# CactusCon7.net
KiCad netlist of a schematic drawn in EAGLE
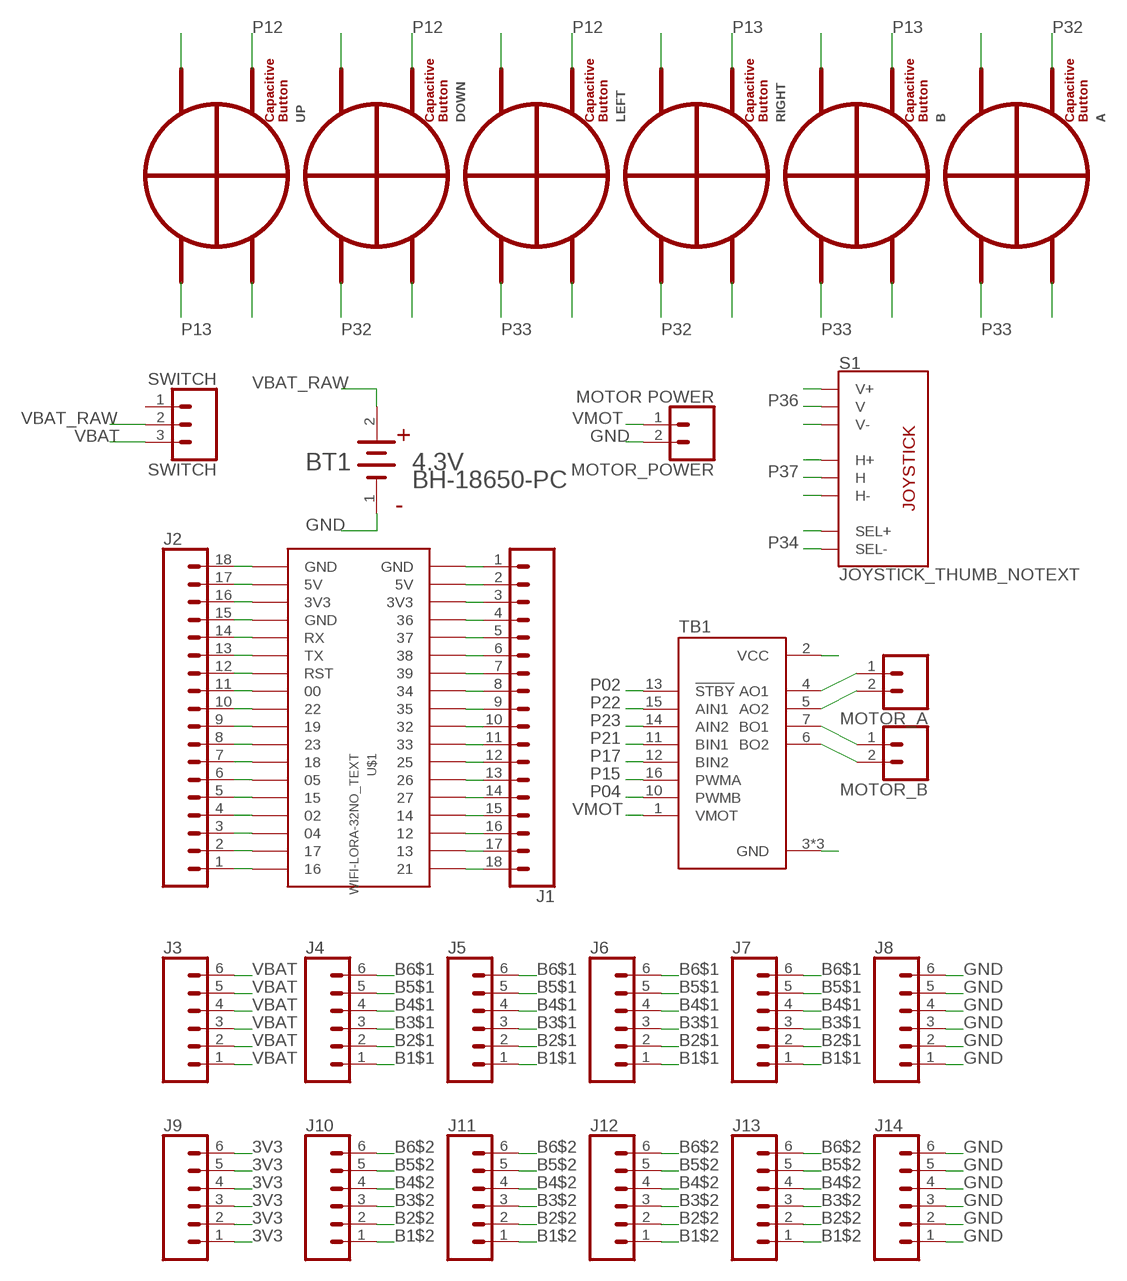
[diagram p0: schematic, sheet 1]

(export (version "E")
  (design (tool "Eeschema 10.0.6"))
  (components
    (comp (ref "A")
      (value "BUTTON_ACTIVE_QUADNO-LOGO")
      (footprint "eagle-import:BUTTON_ACTIVE_QUAD_10MM_NO_LOGO")
      (libsource (lib "eagle-import") (part "BUTTON_ACTIVE_QUADNO-LOGO"))
    )
    (comp (ref "B")
      (value "BUTTON_ACTIVE_QUADNO-LOGO")
      (footprint "eagle-import:BUTTON_ACTIVE_QUAD_10MM_NO_LOGO")
      (libsource (lib "eagle-import") (part "BUTTON_ACTIVE_QUADNO-LOGO"))
    )
    (comp (ref "BT1")
      (value "MPD_BH-18650-PCMPD_BH-18650-PC_0_0")
      (footprint "eagle-import:MPD_BH-18650-PC_0")
      (fields
        (field (name "DIGIKEY_PART_NUMBER") "BH-18650-PC-ND")
        (field (name "MF") "MPD")
        (field (name "MPN") "BH-18650-PC")
      )
      (libsource (lib "eagle-import") (part "MPD_BH-18650-PCMPD_BH-18650-PC_0_0"))
    )
    (comp (ref "DOWN")
      (value "BUTTON_ACTIVE_QUADNO-LOGO")
      (footprint "eagle-import:BUTTON_ACTIVE_QUAD_10MM_NO_LOGO")
      (libsource (lib "eagle-import") (part "BUTTON_ACTIVE_QUADNO-LOGO"))
    )
    (comp (ref "J1")
      (value "CONN_18")
      (footprint "eagle-import:1X18")
      (libsource (lib "eagle-import") (part "CONN_18"))
    )
    (comp (ref "J2")
      (value "CONN_18")
      (footprint "eagle-import:1X18")
      (libsource (lib "eagle-import") (part "CONN_18"))
    )
    (comp (ref "J3")
      (value "CONN_06NO_SILK_FEMALE_PTH")
      (footprint "eagle-import:1X06_NO_SILK")
      (libsource (lib "eagle-import") (part "CONN_06NO_SILK_FEMALE_PTH"))
    )
    (comp (ref "J4")
      (value "CONN_06NO_SILK_FEMALE_PTH")
      (footprint "eagle-import:1X06_NO_SILK")
      (libsource (lib "eagle-import") (part "CONN_06NO_SILK_FEMALE_PTH"))
    )
    (comp (ref "J5")
      (value "CONN_06NO_SILK_FEMALE_PTH")
      (footprint "eagle-import:1X06_NO_SILK")
      (libsource (lib "eagle-import") (part "CONN_06NO_SILK_FEMALE_PTH"))
    )
    (comp (ref "J6")
      (value "CONN_06NO_SILK_FEMALE_PTH")
      (footprint "eagle-import:1X06_NO_SILK")
      (libsource (lib "eagle-import") (part "CONN_06NO_SILK_FEMALE_PTH"))
    )
    (comp (ref "J7")
      (value "CONN_06NO_SILK_FEMALE_PTH")
      (footprint "eagle-import:1X06_NO_SILK")
      (libsource (lib "eagle-import") (part "CONN_06NO_SILK_FEMALE_PTH"))
    )
    (comp (ref "J8")
      (value "CONN_06NO_SILK_FEMALE_PTH")
      (footprint "eagle-import:1X06_NO_SILK")
      (libsource (lib "eagle-import") (part "CONN_06NO_SILK_FEMALE_PTH"))
    )
    (comp (ref "J9")
      (value "CONN_06NO_SILK_FEMALE_PTH")
      (footprint "eagle-import:1X06_NO_SILK")
      (libsource (lib "eagle-import") (part "CONN_06NO_SILK_FEMALE_PTH"))
    )
    (comp (ref "J10")
      (value "CONN_06NO_SILK_FEMALE_PTH")
      (footprint "eagle-import:1X06_NO_SILK")
      (libsource (lib "eagle-import") (part "CONN_06NO_SILK_FEMALE_PTH"))
    )
    (comp (ref "J11")
      (value "CONN_06NO_SILK_FEMALE_PTH")
      (footprint "eagle-import:1X06_NO_SILK")
      (libsource (lib "eagle-import") (part "CONN_06NO_SILK_FEMALE_PTH"))
    )
    (comp (ref "J12")
      (value "CONN_06NO_SILK_FEMALE_PTH")
      (footprint "eagle-import:1X06_NO_SILK")
      (libsource (lib "eagle-import") (part "CONN_06NO_SILK_FEMALE_PTH"))
    )
    (comp (ref "J13")
      (value "CONN_06NO_SILK_FEMALE_PTH")
      (footprint "eagle-import:1X06_NO_SILK")
      (libsource (lib "eagle-import") (part "CONN_06NO_SILK_FEMALE_PTH"))
    )
    (comp (ref "J14")
      (value "CONN_06NO_SILK_FEMALE_PTH")
      (footprint "eagle-import:1X06_NO_SILK")
      (libsource (lib "eagle-import") (part "CONN_06NO_SILK_FEMALE_PTH"))
    )
    (comp (ref "LEFT")
      (value "BUTTON_ACTIVE_QUADNO-LOGO")
      (footprint "eagle-import:BUTTON_ACTIVE_QUAD_10MM_NO_LOGO")
      (libsource (lib "eagle-import") (part "BUTTON_ACTIVE_QUADNO-LOGO"))
    )
    (comp (ref "MOTOR_A")
      (value "CONN_02")
      (footprint "eagle-import:1X02")
      (libsource (lib "eagle-import") (part "CONN_02"))
    )
    (comp (ref "MOTOR_B")
      (value "CONN_02")
      (footprint "eagle-import:1X02")
      (libsource (lib "eagle-import") (part "CONN_02"))
    )
    (comp (ref "MOTOR_POWER")
      (value "MOTOR POWER")
      (footprint "eagle-import:1X02")
      (libsource (lib "eagle-import") (part "CONN_02"))
    )
    (comp (ref "RIGHT")
      (value "BUTTON_ACTIVE_QUADNO-LOGO")
      (footprint "eagle-import:BUTTON_ACTIVE_QUAD_10MM_NO_LOGO")
      (libsource (lib "eagle-import") (part "BUTTON_ACTIVE_QUADNO-LOGO"))
    )
    (comp (ref "S1")
      (value "JOYSTICK_THUMB_NOTEXT")
      (footprint "eagle-import:JOYSTICK")
      (libsource (lib "eagle-import") (part "JOYSTICK_THUMB_NOTEXT"))
    )
    (comp (ref "SWITCH")
      (value "SWITCH")
      (footprint "eagle-import:1X03")
      (libsource (lib "eagle-import") (part "CONN_03"))
    )
    (comp (ref "TB1")
      (value "POLOLU-713ROB-14451")
      (footprint "eagle-import:SHIELD_POLOLU-713")
      (libsource (lib "eagle-import") (part "POLOLU-713ROB-14451"))
    )
    (comp (ref "U$1")
      (value "WIFI-LORA-32NO_TEXT")
      (footprint "eagle-import:2.54MM_2X18_NO_TEXT")
      (libsource (lib "eagle-import") (part "WIFI-LORA-32NO_TEXT"))
    )
    (comp (ref "UP")
      (value "BUTTON_ACTIVE_QUADNO-LOGO")
      (footprint "eagle-import:BUTTON_ACTIVE_QUAD_10MM_NO_LOGO")
      (libsource (lib "eagle-import") (part "BUTTON_ACTIVE_QUADNO-LOGO"))
    )
  )
  (nets
    (net (code "1") (name "/3V3") (class "Default")
      (node (ref "J1") (pin "3") (pinfunction "3_3") (pintype "passive"))
      (node (ref "J2") (pin "16") (pinfunction "16_16") (pintype "passive"))
      (node (ref "J9") (pin "1") (pinfunction "1_1") (pintype "passive"))
      (node (ref "J9") (pin "2") (pinfunction "2_2") (pintype "passive"))
      (node (ref "J9") (pin "3") (pinfunction "3_3") (pintype "passive"))
      (node (ref "J9") (pin "4") (pinfunction "4_4") (pintype "passive"))
      (node (ref "J9") (pin "5") (pinfunction "5_5") (pintype "passive"))
      (node (ref "J9") (pin "6") (pinfunction "6_6") (pintype "passive"))
      (node (ref "S1") (pin "B1A") (pinfunction "SEL+_B1A") (pintype "bidirectional"))
      (node (ref "S1") (pin "H1") (pinfunction "H+_H1") (pintype "bidirectional"))
      (node (ref "S1") (pin "V1") (pinfunction "V+_V1") (pintype "bidirectional"))
      (node (ref "TB1") (pin "2") (pinfunction "VCC_2") (pintype "power_in"))
      (node (ref "U$1") (pin "P$3") (pinfunction "3V3_P$3") (pintype "power_in"))
      (node (ref "U$1") (pin "P$34") (pinfunction "3V3_P$34") (pintype "power_in"))
    )
    (net (code "2") (name "/5V") (class "Default")
      (node (ref "J1") (pin "2") (pinfunction "2_2") (pintype "passive"))
      (node (ref "J2") (pin "17") (pinfunction "17_17") (pintype "passive"))
      (node (ref "U$1") (pin "P$2") (pinfunction "5V_P$2") (pintype "power_in"))
      (node (ref "U$1") (pin "P$35") (pinfunction "5V_P$35") (pintype "power_in"))
    )
    (net (code "3") (name "/B1$1") (class "Default")
      (node (ref "J4") (pin "1") (pinfunction "1_1") (pintype "passive"))
      (node (ref "J5") (pin "1") (pinfunction "1_1") (pintype "passive"))
      (node (ref "J6") (pin "1") (pinfunction "1_1") (pintype "passive"))
      (node (ref "J7") (pin "1") (pinfunction "1_1") (pintype "passive"))
    )
    (net (code "4") (name "/B1$2") (class "Default")
      (node (ref "J10") (pin "1") (pinfunction "1_1") (pintype "passive"))
      (node (ref "J11") (pin "1") (pinfunction "1_1") (pintype "passive"))
      (node (ref "J12") (pin "1") (pinfunction "1_1") (pintype "passive"))
      (node (ref "J13") (pin "1") (pinfunction "1_1") (pintype "passive"))
    )
    (net (code "5") (name "/B2$1") (class "Default")
      (node (ref "J4") (pin "2") (pinfunction "2_2") (pintype "passive"))
      (node (ref "J5") (pin "2") (pinfunction "2_2") (pintype "passive"))
      (node (ref "J6") (pin "2") (pinfunction "2_2") (pintype "passive"))
      (node (ref "J7") (pin "2") (pinfunction "2_2") (pintype "passive"))
    )
    (net (code "6") (name "/B2$2") (class "Default")
      (node (ref "J10") (pin "2") (pinfunction "2_2") (pintype "passive"))
      (node (ref "J11") (pin "2") (pinfunction "2_2") (pintype "passive"))
      (node (ref "J12") (pin "2") (pinfunction "2_2") (pintype "passive"))
      (node (ref "J13") (pin "2") (pinfunction "2_2") (pintype "passive"))
    )
    (net (code "7") (name "/B3$1") (class "Default")
      (node (ref "J4") (pin "3") (pinfunction "3_3") (pintype "passive"))
      (node (ref "J5") (pin "3") (pinfunction "3_3") (pintype "passive"))
      (node (ref "J6") (pin "3") (pinfunction "3_3") (pintype "passive"))
      (node (ref "J7") (pin "3") (pinfunction "3_3") (pintype "passive"))
    )
    (net (code "8") (name "/B3$2") (class "Default")
      (node (ref "J10") (pin "3") (pinfunction "3_3") (pintype "passive"))
      (node (ref "J11") (pin "3") (pinfunction "3_3") (pintype "passive"))
      (node (ref "J12") (pin "3") (pinfunction "3_3") (pintype "passive"))
      (node (ref "J13") (pin "3") (pinfunction "3_3") (pintype "passive"))
    )
    (net (code "9") (name "/B4$1") (class "Default")
      (node (ref "J4") (pin "4") (pinfunction "4_4") (pintype "passive"))
      (node (ref "J5") (pin "4") (pinfunction "4_4") (pintype "passive"))
      (node (ref "J6") (pin "4") (pinfunction "4_4") (pintype "passive"))
      (node (ref "J7") (pin "4") (pinfunction "4_4") (pintype "passive"))
    )
    (net (code "10") (name "/B4$2") (class "Default")
      (node (ref "J10") (pin "4") (pinfunction "4_4") (pintype "passive"))
      (node (ref "J11") (pin "4") (pinfunction "4_4") (pintype "passive"))
      (node (ref "J12") (pin "4") (pinfunction "4_4") (pintype "passive"))
      (node (ref "J13") (pin "4") (pinfunction "4_4") (pintype "passive"))
    )
    (net (code "11") (name "/B5$1") (class "Default")
      (node (ref "J4") (pin "5") (pinfunction "5_5") (pintype "passive"))
      (node (ref "J5") (pin "5") (pinfunction "5_5") (pintype "passive"))
      (node (ref "J6") (pin "5") (pinfunction "5_5") (pintype "passive"))
      (node (ref "J7") (pin "5") (pinfunction "5_5") (pintype "passive"))
    )
    (net (code "12") (name "/B5$2") (class "Default")
      (node (ref "J10") (pin "5") (pinfunction "5_5") (pintype "passive"))
      (node (ref "J11") (pin "5") (pinfunction "5_5") (pintype "passive"))
      (node (ref "J12") (pin "5") (pinfunction "5_5") (pintype "passive"))
      (node (ref "J13") (pin "5") (pinfunction "5_5") (pintype "passive"))
    )
    (net (code "13") (name "/B6$1") (class "Default")
      (node (ref "J4") (pin "6") (pinfunction "6_6") (pintype "passive"))
      (node (ref "J5") (pin "6") (pinfunction "6_6") (pintype "passive"))
      (node (ref "J6") (pin "6") (pinfunction "6_6") (pintype "passive"))
      (node (ref "J7") (pin "6") (pinfunction "6_6") (pintype "passive"))
    )
    (net (code "14") (name "/B6$2") (class "Default")
      (node (ref "J10") (pin "6") (pinfunction "6_6") (pintype "passive"))
      (node (ref "J11") (pin "6") (pinfunction "6_6") (pintype "passive"))
      (node (ref "J12") (pin "6") (pinfunction "6_6") (pintype "passive"))
      (node (ref "J13") (pin "6") (pinfunction "6_6") (pintype "passive"))
    )
    (net (code "15") (name "/GND") (class "Default")
      (node (ref "A") (pin "Q2") (pinfunction "Q2_Q2") (pintype "passive"))
      (node (ref "A") (pin "Q4") (pinfunction "Q4_Q4") (pintype "passive"))
      (node (ref "B") (pin "Q2") (pinfunction "Q2_Q2") (pintype "passive"))
      (node (ref "B") (pin "Q4") (pinfunction "Q4_Q4") (pintype "passive"))
      (node (ref "BT1") (pin "1") (pinfunction "CATHODE_1") (pintype "bidirectional"))
      (node (ref "DOWN") (pin "Q2") (pinfunction "Q2_Q2") (pintype "passive"))
      (node (ref "DOWN") (pin "Q4") (pinfunction "Q4_Q4") (pintype "passive"))
      (node (ref "J1") (pin "1") (pinfunction "1_1") (pintype "passive"))
      (node (ref "J14") (pin "1") (pinfunction "1_1") (pintype "passive"))
      (node (ref "J14") (pin "2") (pinfunction "2_2") (pintype "passive"))
      (node (ref "J14") (pin "3") (pinfunction "3_3") (pintype "passive"))
      (node (ref "J14") (pin "4") (pinfunction "4_4") (pintype "passive"))
      (node (ref "J14") (pin "5") (pinfunction "5_5") (pintype "passive"))
      (node (ref "J14") (pin "6") (pinfunction "6_6") (pintype "passive"))
      (node (ref "J2") (pin "15") (pinfunction "15_15") (pintype "passive"))
      (node (ref "J2") (pin "18") (pinfunction "18_18") (pintype "passive"))
      (node (ref "J8") (pin "1") (pinfunction "1_1") (pintype "passive"))
      (node (ref "J8") (pin "2") (pinfunction "2_2") (pintype "passive"))
      (node (ref "J8") (pin "3") (pinfunction "3_3") (pintype "passive"))
      (node (ref "J8") (pin "4") (pinfunction "4_4") (pintype "passive"))
      (node (ref "J8") (pin "5") (pinfunction "5_5") (pintype "passive"))
      (node (ref "J8") (pin "6") (pinfunction "6_6") (pintype "passive"))
      (node (ref "LEFT") (pin "Q2") (pinfunction "Q2_Q2") (pintype "passive"))
      (node (ref "LEFT") (pin "Q4") (pinfunction "Q4_Q4") (pintype "passive"))
      (node (ref "MOTOR_POWER") (pin "2") (pinfunction "2_2") (pintype "passive"))
      (node (ref "RIGHT") (pin "Q2") (pinfunction "Q2_Q2") (pintype "passive"))
      (node (ref "RIGHT") (pin "Q4") (pinfunction "Q4_Q4") (pintype "passive"))
      (node (ref "S1") (pin "H3") (pinfunction "H-_H3") (pintype "bidirectional"))
      (node (ref "S1") (pin "V3") (pinfunction "V-_V3") (pintype "bidirectional"))
      (node (ref "TB1") (pin "3") (pinfunction "GND_3") (pintype "power_in"))
      (node (ref "TB1") (pin "8") (pinfunction "GND_8") (pintype "power_in"))
      (node (ref "TB1") (pin "9") (pinfunction "GND_9") (pintype "power_in"))
      (node (ref "U$1") (pin "P$1") (pinfunction "GND_P$1") (pintype "power_in"))
      (node (ref "U$1") (pin "P$36") (pinfunction "GND_P$36") (pintype "power_in"))
      (node (ref "U$1") (pin "P$4") (pinfunction "GND_P$4") (pintype "bidirectional"))
      (node (ref "UP") (pin "Q2") (pinfunction "Q2_Q2") (pintype "passive"))
      (node (ref "UP") (pin "Q4") (pinfunction "Q4_Q4") (pintype "passive"))
    )
    (net (code "16") (name "/P02") (class "Default")
      (node (ref "J2") (pin "4") (pinfunction "4_4") (pintype "passive"))
      (node (ref "TB1") (pin "13") (pinfunction "~{STBY}_13") (pintype "input"))
      (node (ref "U$1") (pin "P$15") (pinfunction "02_P$15") (pintype "bidirectional"))
    )
    (net (code "17") (name "/P04") (class "Default")
      (node (ref "J2") (pin "3") (pinfunction "3_3") (pintype "passive"))
      (node (ref "TB1") (pin "10") (pinfunction "PWMB_10") (pintype "input"))
      (node (ref "U$1") (pin "P$16") (pinfunction "04_P$16") (pintype "bidirectional"))
    )
    (net (code "18") (name "/P12") (class "Default")
      (node (ref "DOWN") (pin "Q3") (pinfunction "Q3_Q3") (pintype "passive"))
      (node (ref "J1") (pin "16") (pinfunction "16_16") (pintype "passive"))
      (node (ref "LEFT") (pin "Q3") (pinfunction "Q3_Q3") (pintype "passive"))
      (node (ref "U$1") (pin "P$21") (pinfunction "12_P$21") (pintype "bidirectional"))
      (node (ref "UP") (pin "Q3") (pinfunction "Q3_Q3") (pintype "passive"))
    )
    (net (code "19") (name "/P13") (class "Default")
      (node (ref "B") (pin "Q3") (pinfunction "Q3_Q3") (pintype "passive"))
      (node (ref "J1") (pin "17") (pinfunction "17_17") (pintype "passive"))
      (node (ref "RIGHT") (pin "Q3") (pinfunction "Q3_Q3") (pintype "passive"))
      (node (ref "U$1") (pin "P$20") (pinfunction "13_P$20") (pintype "bidirectional"))
      (node (ref "UP") (pin "Q1") (pinfunction "Q1_Q1") (pintype "passive"))
    )
    (net (code "20") (name "/P15") (class "Default")
      (node (ref "J2") (pin "5") (pinfunction "5_5") (pintype "passive"))
      (node (ref "TB1") (pin "16") (pinfunction "PWMA_16") (pintype "input"))
      (node (ref "U$1") (pin "P$14") (pinfunction "15_P$14") (pintype "bidirectional"))
    )
    (net (code "21") (name "/P17") (class "Default")
      (node (ref "J2") (pin "2") (pinfunction "2_2") (pintype "passive"))
      (node (ref "TB1") (pin "12") (pinfunction "BIN2_12") (pintype "input"))
      (node (ref "U$1") (pin "P$17") (pinfunction "17_P$17") (pintype "bidirectional"))
    )
    (net (code "22") (name "/P21") (class "Default")
      (node (ref "J1") (pin "18") (pinfunction "18_18") (pintype "passive"))
      (node (ref "TB1") (pin "11") (pinfunction "BIN1_11") (pintype "input"))
      (node (ref "U$1") (pin "P$19") (pinfunction "21_P$19") (pintype "bidirectional"))
    )
    (net (code "23") (name "/P22") (class "Default")
      (node (ref "J2") (pin "10") (pinfunction "10_10") (pintype "passive"))
      (node (ref "TB1") (pin "15") (pinfunction "AIN1_15") (pintype "input"))
      (node (ref "U$1") (pin "P$9") (pinfunction "22_P$9") (pintype "bidirectional"))
    )
    (net (code "24") (name "/P23") (class "Default")
      (node (ref "J2") (pin "8") (pinfunction "8_8") (pintype "passive"))
      (node (ref "TB1") (pin "14") (pinfunction "AIN2_14") (pintype "input"))
      (node (ref "U$1") (pin "P$11") (pinfunction "23_P$11") (pintype "bidirectional"))
    )
    (net (code "25") (name "/P32") (class "Default")
      (node (ref "A") (pin "Q3") (pinfunction "Q3_Q3") (pintype "passive"))
      (node (ref "DOWN") (pin "Q1") (pinfunction "Q1_Q1") (pintype "passive"))
      (node (ref "J1") (pin "10") (pinfunction "10_10") (pintype "passive"))
      (node (ref "RIGHT") (pin "Q1") (pinfunction "Q1_Q1") (pintype "passive"))
      (node (ref "U$1") (pin "P$27") (pinfunction "32_P$27") (pintype "bidirectional"))
    )
    (net (code "26") (name "/P33") (class "Default")
      (node (ref "A") (pin "Q1") (pinfunction "Q1_Q1") (pintype "passive"))
      (node (ref "B") (pin "Q1") (pinfunction "Q1_Q1") (pintype "passive"))
      (node (ref "J1") (pin "11") (pinfunction "11_11") (pintype "passive"))
      (node (ref "LEFT") (pin "Q1") (pinfunction "Q1_Q1") (pintype "passive"))
      (node (ref "U$1") (pin "P$26") (pinfunction "33_P$26") (pintype "bidirectional"))
    )
    (net (code "27") (name "/P34") (class "Default")
      (node (ref "J1") (pin "8") (pinfunction "8_8") (pintype "passive"))
      (node (ref "S1") (pin "B2A") (pinfunction "SEL-_B2A") (pintype "bidirectional"))
      (node (ref "U$1") (pin "P$29") (pinfunction "34_P$29") (pintype "bidirectional"))
    )
    (net (code "28") (name "/P36") (class "Default")
      (node (ref "J1") (pin "4") (pinfunction "4_4") (pintype "passive"))
      (node (ref "S1") (pin "V2") (pinfunction "V_V2") (pintype "bidirectional"))
      (node (ref "U$1") (pin "P$33") (pinfunction "36_P$33") (pintype "bidirectional"))
    )
    (net (code "29") (name "/P37") (class "Default")
      (node (ref "J1") (pin "5") (pinfunction "5_5") (pintype "passive"))
      (node (ref "S1") (pin "H2") (pinfunction "H_H2") (pintype "bidirectional"))
      (node (ref "U$1") (pin "P$32") (pinfunction "37_P$32") (pintype "bidirectional"))
    )
    (net (code "30") (name "/VBAT") (class "Default")
      (node (ref "J3") (pin "1") (pinfunction "1_1") (pintype "passive"))
      (node (ref "J3") (pin "2") (pinfunction "2_2") (pintype "passive"))
      (node (ref "J3") (pin "3") (pinfunction "3_3") (pintype "passive"))
      (node (ref "J3") (pin "4") (pinfunction "4_4") (pintype "passive"))
      (node (ref "J3") (pin "5") (pinfunction "5_5") (pintype "passive"))
      (node (ref "J3") (pin "6") (pinfunction "6_6") (pintype "passive"))
      (node (ref "SWITCH") (pin "3") (pinfunction "3_3") (pintype "passive"))
    )
    (net (code "31") (name "/VBAT_RAW") (class "Default")
      (node (ref "BT1") (pin "2") (pinfunction "ANODE_2") (pintype "bidirectional"))
      (node (ref "SWITCH") (pin "2") (pinfunction "2_2") (pintype "passive"))
    )
    (net (code "32") (name "/VMOT") (class "Default")
      (node (ref "MOTOR_POWER") (pin "1") (pinfunction "1_1") (pintype "passive"))
      (node (ref "TB1") (pin "1") (pinfunction "VMOT_1") (pintype "input"))
    )
    (net (code "33") (name "Net-(TB1-AO1)") (class "Default")
      (node (ref "MOTOR_A") (pin "1") (pinfunction "1_1") (pintype "passive"))
      (node (ref "TB1") (pin "4") (pinfunction "AO1_4") (pintype "output"))
    )
    (net (code "34") (name "Net-(TB1-AO2)") (class "Default")
      (node (ref "MOTOR_A") (pin "2") (pinfunction "2_2") (pintype "passive"))
      (node (ref "TB1") (pin "5") (pinfunction "AO2_5") (pintype "output"))
    )
    (net (code "35") (name "Net-(TB1-BO1)") (class "Default")
      (node (ref "MOTOR_B") (pin "1") (pinfunction "1_1") (pintype "passive"))
      (node (ref "TB1") (pin "7") (pinfunction "BO1_7") (pintype "output"))
    )
    (net (code "36") (name "Net-(TB1-BO2)") (class "Default")
      (node (ref "MOTOR_B") (pin "2") (pinfunction "2_2") (pintype "passive"))
      (node (ref "TB1") (pin "6") (pinfunction "BO2_6") (pintype "output"))
    )
    (net (code "37") (name "Net-(U$1-00)") (class "Default")
      (node (ref "J2") (pin "11") (pinfunction "11_11") (pintype "passive"))
      (node (ref "U$1") (pin "P$8") (pinfunction "00_P$8") (pintype "bidirectional"))
    )
    (net (code "38") (name "Net-(U$1-05)") (class "Default")
      (node (ref "J2") (pin "6") (pinfunction "6_6") (pintype "passive"))
      (node (ref "U$1") (pin "P$13") (pinfunction "05_P$13") (pintype "bidirectional"))
    )
    (net (code "39") (name "Net-(U$1-14)") (class "Default")
      (node (ref "J1") (pin "15") (pinfunction "15_15") (pintype "passive"))
      (node (ref "U$1") (pin "P$22") (pinfunction "14_P$22") (pintype "bidirectional"))
    )
    (net (code "40") (name "Net-(U$1-16)") (class "Default")
      (node (ref "J2") (pin "1") (pinfunction "1_1") (pintype "passive"))
      (node (ref "U$1") (pin "P$18") (pinfunction "16_P$18") (pintype "bidirectional"))
    )
    (net (code "41") (name "Net-(U$1-18)") (class "Default")
      (node (ref "J2") (pin "7") (pinfunction "7_7") (pintype "passive"))
      (node (ref "U$1") (pin "P$12") (pinfunction "18_P$12") (pintype "bidirectional"))
    )
    (net (code "42") (name "Net-(U$1-19)") (class "Default")
      (node (ref "J2") (pin "9") (pinfunction "9_9") (pintype "passive"))
      (node (ref "U$1") (pin "P$10") (pinfunction "19_P$10") (pintype "bidirectional"))
    )
    (net (code "43") (name "Net-(U$1-25)") (class "Default")
      (node (ref "J1") (pin "12") (pinfunction "12_12") (pintype "passive"))
      (node (ref "U$1") (pin "P$25") (pinfunction "25_P$25") (pintype "bidirectional"))
    )
    (net (code "44") (name "Net-(U$1-26)") (class "Default")
      (node (ref "J1") (pin "13") (pinfunction "13_13") (pintype "passive"))
      (node (ref "U$1") (pin "P$24") (pinfunction "26_P$24") (pintype "bidirectional"))
    )
    (net (code "45") (name "Net-(U$1-27)") (class "Default")
      (node (ref "J1") (pin "14") (pinfunction "14_14") (pintype "passive"))
      (node (ref "U$1") (pin "P$23") (pinfunction "27_P$23") (pintype "bidirectional"))
    )
    (net (code "46") (name "Net-(U$1-35)") (class "Default")
      (node (ref "J1") (pin "9") (pinfunction "9_9") (pintype "passive"))
      (node (ref "U$1") (pin "P$28") (pinfunction "35_P$28") (pintype "bidirectional"))
    )
    (net (code "47") (name "Net-(U$1-38)") (class "Default")
      (node (ref "J1") (pin "6") (pinfunction "6_6") (pintype "passive"))
      (node (ref "U$1") (pin "P$31") (pinfunction "38_P$31") (pintype "bidirectional"))
    )
    (net (code "48") (name "Net-(U$1-39)") (class "Default")
      (node (ref "J1") (pin "7") (pinfunction "7_7") (pintype "passive"))
      (node (ref "U$1") (pin "P$30") (pinfunction "39_P$30") (pintype "bidirectional"))
    )
    (net (code "49") (name "Net-(U$1-RST)") (class "Default")
      (node (ref "J2") (pin "12") (pinfunction "12_12") (pintype "passive"))
      (node (ref "U$1") (pin "P$7") (pinfunction "RST_P$7") (pintype "bidirectional"))
    )
    (net (code "50") (name "Net-(U$1-RX)") (class "Default")
      (node (ref "J2") (pin "14") (pinfunction "14_14") (pintype "passive"))
      (node (ref "U$1") (pin "P$5") (pinfunction "RX_P$5") (pintype "bidirectional"))
    )
    (net (code "51") (name "Net-(U$1-TX)") (class "Default")
      (node (ref "J2") (pin "13") (pinfunction "13_13") (pintype "passive"))
      (node (ref "U$1") (pin "P$6") (pinfunction "TX_P$6") (pintype "bidirectional"))
    )
    (net (code "52") (name "unconnected-(SWITCH-Pad1)") (class "Default")
      (node (ref "SWITCH") (pin "1") (pinfunction "1_1") (pintype "passive"))
    )
  )
)
